# PS2_CONECTOR.net
KiCad netlist of a schematic drawn in Altium Designer
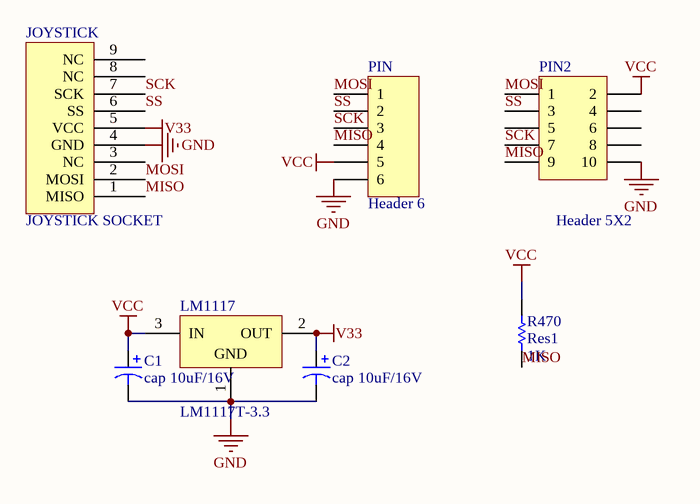
[diagram p0: PS2 CONECTOR.SchDoc]

(export (version "E")
  (design (tool "Eeschema 10.0.6"))
  (components
    (comp (ref "C1")
      (value "cap 10uF/16V")
      (footprint "cap 10uF/16V")
      (libsource (lib "agfa other components") (part "cap 10uF/16V"))
    )
    (comp (ref "C2")
      (value "cap 10uF/16V")
      (footprint "cap 10uF/16V")
      (libsource (lib "agfa other components") (part "cap 10uF/16V"))
    )
    (comp (ref "JOYSTICK")
      (value "JOYSTICK SOCKET")
      (footprint "JOY SOCKET")
      (libsource (lib "Library Ausiher") (part "Socket joystick"))
    )
    (comp (ref "LM1117")
      (value "LM1117T-3.3")
      (footprint "T03B")
      (description "800mA Low-Dropout Linear Regulator, 3-pin TO-220")
      (fields
        (field (name "MANUFACTURER") "National Semiconductor")
        (field (name "PUBLISHER") "Altium Limited")
      )
      (libsource (lib "NSC LDO") (part "LM1117T-3.3"))
    )
    (comp (ref "PIN")
      (value "Header 6")
      (footprint "HDR1X6")
      (description "Header, 6-Pin")
      (fields (field (name "PUBLISHER") "Altium Limited"))
      (libsource (lib "Miscellaneous Connectors") (part "Header 6"))
    )
    (comp (ref "PIN2")
      (value "Header 5X2")
      (footprint "HDR2X5")
      (description "Header, 5-Pin, Dual row")
      (fields (field (name "PUBLISHER") "Altium Limited"))
      (libsource (lib "Miscellaneous Connectors") (part "Header 5X2"))
    )
    (comp (ref "R470")
      (value "Res1")
      (footprint "AXIAL-0.3")
      (description "Resistor")
      (fields (field (name "ALTIUM_VALUE") "1K") (field (name "PUBLISHER") "Altium Limited"))
      (libsource (lib "Miscellaneous Devices") (part "Res1"))
    )
  )
  (nets
    (net (code "1") (name "/MISO") (class "Default")
      (node (ref "JOYSTICK") (pin "1") (pinfunction "MISO_1") (pintype "passive"))
      (node (ref "PIN") (pin "4") (pinfunction "4_4") (pintype "passive"))
      (node (ref "PIN2") (pin "9") (pinfunction "9_9") (pintype "passive"))
      (node (ref "R470") (pin "1") (pinfunction "1_1") (pintype "passive"))
    )
    (net (code "2") (name "/MOSI") (class "Default")
      (node (ref "JOYSTICK") (pin "2") (pinfunction "MOSI_2") (pintype "passive"))
      (node (ref "PIN") (pin "1") (pinfunction "1_1") (pintype "passive"))
      (node (ref "PIN2") (pin "1") (pinfunction "1_1") (pintype "passive"))
    )
    (net (code "3") (name "/SCK") (class "Default")
      (node (ref "JOYSTICK") (pin "7") (pinfunction "SCK_7") (pintype "passive"))
      (node (ref "PIN") (pin "3") (pinfunction "3_3") (pintype "passive"))
      (node (ref "PIN2") (pin "7") (pinfunction "7_7") (pintype "passive"))
    )
    (net (code "4") (name "/SS") (class "Default")
      (node (ref "JOYSTICK") (pin "6") (pinfunction "SS_6") (pintype "passive"))
      (node (ref "PIN") (pin "2") (pinfunction "2_2") (pintype "passive"))
      (node (ref "PIN2") (pin "3") (pinfunction "3_3") (pintype "passive"))
    )
    (net (code "5") (name "GND") (class "Default")
      (node (ref "C1") (pin "2") (pinfunction "2_2") (pintype "passive"))
      (node (ref "C2") (pin "2") (pinfunction "2_2") (pintype "passive"))
      (node (ref "JOYSTICK") (pin "4") (pinfunction "GND_4") (pintype "passive"))
      (node (ref "LM1117") (pin "1") (pinfunction "GND_1") (pintype "power_in"))
      (node (ref "PIN") (pin "6") (pinfunction "6_6") (pintype "passive"))
      (node (ref "PIN2") (pin "10") (pinfunction "10_10") (pintype "passive"))
    )
    (net (code "6") (name "V33") (class "Default")
      (node (ref "C2") (pin "1") (pinfunction "1_1") (pintype "passive"))
      (node (ref "JOYSTICK") (pin "5") (pinfunction "VCC_5") (pintype "passive"))
      (node (ref "LM1117") (pin "2") (pinfunction "OUT_2") (pintype "power_in"))
    )
    (net (code "7") (name "VCC") (class "Default")
      (node (ref "C1") (pin "1") (pinfunction "1_1") (pintype "passive"))
      (node (ref "LM1117") (pin "3") (pinfunction "IN_3") (pintype "power_in"))
      (node (ref "PIN") (pin "5") (pinfunction "5_5") (pintype "passive"))
      (node (ref "PIN2") (pin "2") (pinfunction "2_2") (pintype "passive"))
      (node (ref "R470") (pin "2") (pinfunction "2_2") (pintype "passive"))
    )
    (net (code "8") (name "unconnected-(JOYSTICK-NC-Pad3)") (class "Default")
      (node (ref "JOYSTICK") (pin "3") (pinfunction "NC_3") (pintype "passive"))
    )
    (net (code "9") (name "unconnected-(JOYSTICK-NC-Pad8)") (class "Default")
      (node (ref "JOYSTICK") (pin "8") (pinfunction "NC_8") (pintype "passive"))
    )
    (net (code "10") (name "unconnected-(JOYSTICK-NC-Pad9)") (class "Default")
      (node (ref "JOYSTICK") (pin "9") (pinfunction "NC_9") (pintype "passive"))
    )
    (net (code "11") (name "unconnected-(PIN2-Pad4)") (class "Default")
      (node (ref "PIN2") (pin "4") (pinfunction "4_4") (pintype "passive"))
    )
    (net (code "12") (name "unconnected-(PIN2-Pad5)") (class "Default")
      (node (ref "PIN2") (pin "5") (pinfunction "5_5") (pintype "passive"))
    )
    (net (code "13") (name "unconnected-(PIN2-Pad6)") (class "Default")
      (node (ref "PIN2") (pin "6") (pinfunction "6_6") (pintype "passive"))
    )
    (net (code "14") (name "unconnected-(PIN2-Pad8)") (class "Default")
      (node (ref "PIN2") (pin "8") (pinfunction "8_8") (pintype "passive"))
    )
  )
)
